# Output.net
KiCad netlist of a schematic drawn in Altium Designer
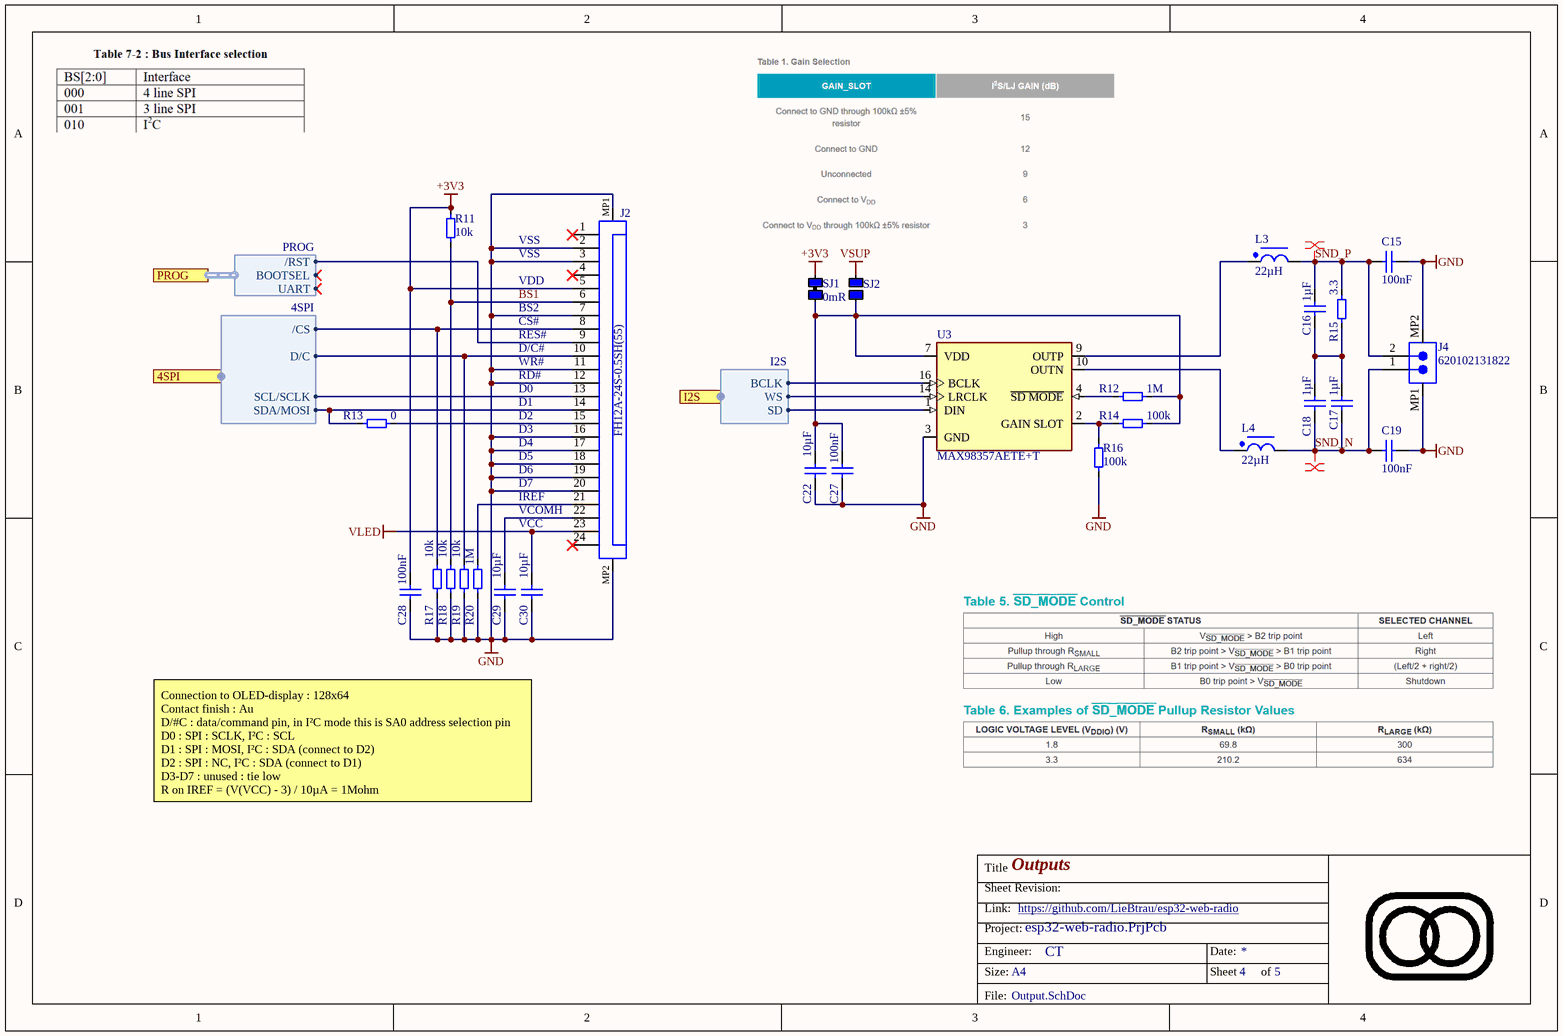
[diagram p0: Output.SchDoc]

(export (version "E")
  (design (tool "Eeschema 10.0.6"))
  (components
    (comp (ref "C15")
      (value "100nF")
      (footprint "0603-C-N")
      (description "WCAP-CSGP Multilayer Ceramic Chip Capacitor, General Purpose, size 0603, X7R, 100nF, 50VDC")
      (fields (field (name "TOLERANCE") "10%") (field (name "JLCPCB PART #") "C14663"))
      (libsource (lib "7c7 Engineering") (part "CAP-NP-2"))
    )
    (comp (ref "C16")
      (value "1µF")
      (footprint "0805-C-N")
      (description "WCAP-CSGP Multilayer Ceramic Chip Capacitor, General Purpose, size 0805, X7R, 1µF, 10VDC")
      (fields (field (name "TOLERANCE") "10%") (field (name "JLCPCB PART #") "C28323"))
      (libsource (lib "7c7 Engineering") (part "CAP-NP-2"))
    )
    (comp (ref "C17")
      (value "1µF")
      (footprint "0805-C-N")
      (description "WCAP-CSGP Multilayer Ceramic Chip Capacitor, General Purpose, size 0805, X7R, 1µF, 10VDC")
      (fields (field (name "TOLERANCE") "10%") (field (name "JLCPCB PART #") "C28323"))
      (libsource (lib "7c7 Engineering") (part "CAP-NP-2"))
    )
    (comp (ref "C18")
      (value "1µF")
      (footprint "0805-C-N")
      (description "WCAP-CSGP Multilayer Ceramic Chip Capacitor, General Purpose, size 0805, X7R, 1µF, 10VDC")
      (fields (field (name "TOLERANCE") "10%") (field (name "JLCPCB PART #") "C28323"))
      (libsource (lib "7c7 Engineering") (part "CAP-NP-2"))
    )
    (comp (ref "C19")
      (value "100nF")
      (footprint "0603-C-N")
      (description "WCAP-CSGP Multilayer Ceramic Chip Capacitor, General Purpose, size 0603, X7R, 100nF, 50VDC")
      (fields (field (name "TOLERANCE") "10%") (field (name "JLCPCB PART #") "C14663"))
      (libsource (lib "7c7 Engineering") (part "CAP-NP-2"))
    )
    (comp (ref "C22")
      (value "10µF")
      (footprint "1206-C-N")
      (description "WCAP-CSGP Multilayer Ceramic Chip Capacitor, General Purpose, size 1206, X7R, 10µF, 10VDC")
      (fields (field (name "TOLERANCE") "10%") (field (name "JLCPCB PART #") "C97953"))
      (libsource (lib "7c7 Engineering") (part "CAP-NP-2"))
    )
    (comp (ref "C27")
      (value "100nF")
      (footprint "0603-C-N")
      (description "WCAP-CSGP Multilayer Ceramic Chip Capacitor, General Purpose, size 0603, X7R, 100nF, 50VDC")
      (fields (field (name "TOLERANCE") "10%") (field (name "JLCPCB PART #") "C14663"))
      (libsource (lib "7c7 Engineering") (part "CAP-NP-2"))
    )
    (comp (ref "C28")
      (value "100nF")
      (footprint "0603-C-N")
      (description "WCAP-CSGP Multilayer Ceramic Chip Capacitor, General Purpose, size 0603, X7R, 100nF, 50VDC")
      (fields (field (name "TOLERANCE") "10%") (field (name "JLCPCB PART #") "C14663"))
      (libsource (lib "7c7 Engineering") (part "CAP-NP-2"))
    )
    (comp (ref "C29")
      (value "10µF")
      (footprint "WCAP-CSGP_1210_L3.2W2.5H2.5")
      (description "WCAP-CSGP Multilayer Ceramic Chip Capacitor, General Purpose, size 1210, X7R, 10µF, 50VDC")
      (fields (field (name "JLCPCB PART #") "C2918502") (field (name "TOLERANCE") "10%"))
      (libsource (lib "7c7 Engineering") (part "CAP-NP-2"))
    )
    (comp (ref "C30")
      (value "10µF")
      (footprint "1206-C-N")
      (description "WCAP-CSGP Multilayer Ceramic Chip Capacitor, General Purpose, size 1206, X7R, 10µF, 10VDC")
      (fields (field (name "TOLERANCE") "10%") (field (name "JLCPCB PART #") "C97953"))
      (libsource (lib "7c7 Engineering") (part "CAP-NP-2"))
    )
    (comp (ref "J2")
      (value "FH12A-24S-0.5SH(55)")
      (footprint "CF20241U0R0-NH")
      (description "Conn Ffc/fpc Connector Skt 24 Pos 0.5MM Solder Ra SMD T/r / Conn Ffc Top 24POS 0.50MM R/a")
      (fields (field (name "JLCPCB PART #") "C506794"))
      (libsource (lib "7c7 Engineering") (part "FFC_24P"))
    )
    (comp (ref "J4")
      (value "620102131822")
      (footprint "620102131822")
      (description "WR-WTB SMT Male Horizontal Shrouded Header, pitch 2mm, 2p")
      (fields (field (name "JLCPCB PART #") "C295747") (field (name "PUBLISHER") "Wurth Elektronik"))
      (libsource (lib "7c7 Engineering") (part "HDR_2P_2MP"))
    )
    (comp (ref "L3")
      (value "74404063220")
      (footprint "WE-LQS_6028")
      (description "WE-LQS SMT Power Inductor, size 6028, 22µH, 1.4A, 0.14O")
      (fields
        (field (name "INDUCTANCE") "22µH")
        (field (name "JLCPCB PART #") "C668454")
        (field (name "MANUFACTURER") "Wurth Elektronik")
      )
      (libsource (lib "7c7 Engineering") (part "IND-CORE-2"))
    )
    (comp (ref "L4")
      (value "74404063220")
      (footprint "WE-LQS_6028")
      (description "WE-LQS SMT Power Inductor, size 6028, 22µH, 1.4A, 0.14O")
      (fields
        (field (name "INDUCTANCE") "22µH")
        (field (name "JLCPCB PART #") "C668454")
        (field (name "MANUFACTURER") "Wurth Elektronik")
      )
      (libsource (lib "7c7 Engineering") (part "IND-CORE-2"))
    )
    (comp (ref "R11")
      (value "10k")
      (footprint "0603-R-N")
      (description "Chip Resistor, Thick Film, General Purpose, 0603, 100mW, 50V, 10 kOhm, +/-1%")
      (fields (field (name "JLCPCB PART #") "C25804") (field (name "TOLERANCE") "1%"))
      (libsource (lib "7c7 Engineering") (part "RES"))
    )
    (comp (ref "R12")
      (value "1M")
      (footprint "0603-R-N")
      (description "Chip Resistor, Thick Film, General Purpose, 0603, 100mW, 50V, 1 MOhm, +/-1%")
      (fields (field (name "TOLERANCE") "1%") (field (name "JLCPCB PART #") "C22935"))
      (libsource (lib "") (part "RES_1"))
    )
    (comp (ref "R13")
      (value "0")
      (footprint "0603-R-N")
      (description "Chip Jumper, Thick Film, Jumper, 0603, 100mW, 1A, 0 Ohm, <50 mOhm")
      (fields (field (name "TOLERANCE") "50 mOhm") (field (name "JLCPCB PART #") "C21189"))
      (libsource (lib "") (part "RES_1"))
    )
    (comp (ref "R14")
      (value "100k")
      (footprint "0603-R-N")
      (description "Chip Resistor, Thick Film, General Purpose, 0603, 100mW, 50V, 100 kOhm, +/-1%")
      (fields (field (name "TOLERANCE") "1%") (field (name "JLCPCB PART #") "C25803"))
      (libsource (lib "") (part "RES_2"))
    )
    (comp (ref "R15")
      (value "3.3")
      (footprint "1206-R-N")
      (description "Res Thick Film 1206 3.3 Ohm 1% 1/4W ±200ppm/°C Molded SMD SMD Paper T/R")
      (fields (field (name "JLCPCB PART #") "C17945") (field (name "TOLERANCE") "1%"))
      (libsource (lib "7c7 Engineering") (part "RES"))
    )
    (comp (ref "R16")
      (value "100k")
      (footprint "0603-R-N")
      (description "Chip Resistor, Thick Film, General Purpose, 0603, 100mW, 50V, 100 kOhm, +/-1%")
      (fields (field (name "TOLERANCE") "1%") (field (name "JLCPCB PART #") "C25803"))
      (libsource (lib "7c7 Engineering") (part "RES"))
    )
    (comp (ref "R17")
      (value "10k")
      (footprint "0603-R-N")
      (description "Chip Resistor, Thick Film, General Purpose, 0603, 100mW, 50V, 10 kOhm, +/-1%")
      (fields (field (name "JLCPCB PART #") "C25804") (field (name "TOLERANCE") "1%"))
      (libsource (lib "7c7 Engineering") (part "RES"))
    )
    (comp (ref "R18")
      (value "10k")
      (footprint "0603-R-N")
      (description "Chip Resistor, Thick Film, General Purpose, 0603, 100mW, 50V, 10 kOhm, +/-1%")
      (fields (field (name "JLCPCB PART #") "C25804") (field (name "TOLERANCE") "1%"))
      (libsource (lib "7c7 Engineering") (part "RES"))
    )
    (comp (ref "R19")
      (value "10k")
      (footprint "0603-R-N")
      (description "Chip Resistor, Thick Film, General Purpose, 0603, 100mW, 50V, 10 kOhm, +/-1%")
      (fields (field (name "JLCPCB PART #") "C25804") (field (name "TOLERANCE") "1%"))
      (libsource (lib "7c7 Engineering") (part "RES"))
    )
    (comp (ref "R20")
      (value "1M")
      (footprint "0603-R-N")
      (description "Chip Resistor, Thick Film, General Purpose, 0603, 100mW, 50V, 1 MOhm, +/-1%")
      (fields (field (name "TOLERANCE") "1%") (field (name "JLCPCB PART #") "C22935"))
      (libsource (lib "7c7 Engineering") (part "RES"))
    )
    (comp (ref "SJ1")
      (value "0mR")
      (footprint "SJ_0603_1A")
      (description "Solder jumper 0603 1A")
      (fields (field (name "JLCPCB PART #") "C876125") (field (name "TOLERANCE") "1%"))
      (libsource (lib "7c7 Engineering") (part "SJ-C"))
    )
    (comp (ref "SJ2")
      (value "Solder jumper open 1A")
      (footprint "Solder jumper open 1A-Footprint-1")
      (libsource (lib "7c7 Engineering") (part "SJ-O"))
    )
    (comp (ref "U3")
      (value "MAX98357AETE+T")
      (footprint "TQFN16-MFG")
      (description "IC AUDIO AMP CLASS D 16-TQFN")
      (fields (field (name "JLCPCB PART #") "C910544"))
      (libsource (lib "7c7 Engineering") (part "MAX98357A"))
    )
  )
  (nets
    (net (code "4") (name "+3V3") (class "Default")
      (node (ref "C28") (pin "1") (pinfunction "1_1") (pintype "passive"))
      (node (ref "J2") (pin "5") (pinfunction "5_5") (pintype "passive"))
      (node (ref "R11") (pin "2") (pinfunction "2_2") (pintype "passive"))
      (node (ref "SJ1") (pin "2") (pinfunction "R_2") (pintype "passive"))
    )
    (net (code "5") (name "/BS1") (class "Default")
      (node (ref "J2") (pin "6") (pinfunction "6_6") (pintype "passive"))
      (node (ref "R11") (pin "1") (pinfunction "1_1") (pintype "passive"))
      (node (ref "R18") (pin "2") (pinfunction "2_2") (pintype "passive"))
    )
    (net (code "6") (name "/SND_N") (class "Default")
      (node (ref "C17") (pin "1") (pinfunction "1_1") (pintype "passive"))
      (node (ref "C18") (pin "1") (pinfunction "1_1") (pintype "passive"))
      (node (ref "C19") (pin "1") (pinfunction "1_1") (pintype "passive"))
      (node (ref "J4") (pin "1") (pinfunction "1_1") (pintype "passive"))
      (node (ref "L4") (pin "2") (pinfunction "2_2") (pintype "passive"))
    )
    (net (code "7") (name "/SND_P") (class "Default")
      (node (ref "C15") (pin "1") (pinfunction "1_1") (pintype "passive"))
      (node (ref "C16") (pin "2") (pinfunction "2_2") (pintype "passive"))
      (node (ref "J4") (pin "2") (pinfunction "2_2") (pintype "passive"))
      (node (ref "L3") (pin "2") (pinfunction "2_2") (pintype "passive"))
      (node (ref "R15") (pin "2") (pinfunction "2_2") (pintype "passive"))
    )
    (net (code "11") (name "GND") (class "Default")
      (node (ref "C15") (pin "2") (pinfunction "2_2") (pintype "passive"))
      (node (ref "C19") (pin "2") (pinfunction "2_2") (pintype "passive"))
      (node (ref "C22") (pin "1") (pinfunction "1_1") (pintype "passive"))
      (node (ref "C27") (pin "1") (pinfunction "1_1") (pintype "passive"))
      (node (ref "C28") (pin "2") (pinfunction "2_2") (pintype "passive"))
      (node (ref "C29") (pin "1") (pinfunction "1_1") (pintype "passive"))
      (node (ref "C30") (pin "1") (pinfunction "1_1") (pintype "passive"))
      (node (ref "J2") (pin "11") (pinfunction "11_11") (pintype "passive"))
      (node (ref "J2") (pin "12") (pinfunction "12_12") (pintype "passive"))
      (node (ref "J2") (pin "16") (pinfunction "16_16") (pintype "passive"))
      (node (ref "J2") (pin "17") (pinfunction "17_17") (pintype "passive"))
      (node (ref "J2") (pin "18") (pinfunction "18_18") (pintype "passive"))
      (node (ref "J2") (pin "19") (pinfunction "19_19") (pintype "passive"))
      (node (ref "J2") (pin "2") (pinfunction "2_2") (pintype "passive"))
      (node (ref "J2") (pin "20") (pinfunction "20_20") (pintype "passive"))
      (node (ref "J2") (pin "3") (pinfunction "3_3") (pintype "passive"))
      (node (ref "J2") (pin "7") (pinfunction "7_7") (pintype "passive"))
      (node (ref "J2") (pin "MP1") (pinfunction "MP1_MP1") (pintype "passive"))
      (node (ref "J2") (pin "MP2") (pinfunction "MP2_MP2") (pintype "passive"))
      (node (ref "J4") (pin "MP1") (pinfunction "MP1_MP1") (pintype "passive"))
      (node (ref "J4") (pin "MP2") (pinfunction "MP2_MP2") (pintype "passive"))
      (node (ref "R16") (pin "1") (pinfunction "1_1") (pintype "passive"))
      (node (ref "R17") (pin "1") (pinfunction "1_1") (pintype "passive"))
      (node (ref "R18") (pin "1") (pinfunction "1_1") (pintype "passive"))
      (node (ref "R19") (pin "1") (pinfunction "1_1") (pintype "passive"))
      (node (ref "R20") (pin "1") (pinfunction "1_1") (pintype "passive"))
      (node (ref "U3") (pin "3") (pinfunction "GND_3") (pintype "power_in"))
    )
    (net (code "12") (name "Net-(C16-Pad1)") (class "Default")
      (node (ref "C16") (pin "1") (pinfunction "1_1") (pintype "passive"))
      (node (ref "C17") (pin "2") (pinfunction "2_2") (pintype "passive"))
      (node (ref "C18") (pin "2") (pinfunction "2_2") (pintype "passive"))
      (node (ref "R15") (pin "1") (pinfunction "1_1") (pintype "passive"))
    )
    (net (code "13") (name "Net-(C29-Pad2)") (class "Default")
      (node (ref "C29") (pin "2") (pinfunction "2_2") (pintype "passive"))
      (node (ref "J2") (pin "22") (pinfunction "22_22") (pintype "passive"))
    )
    (net (code "14") (name "Net-(J2-Pad8)") (class "Default")
      (node (ref "J2") (pin "8") (pinfunction "8_8") (pintype "passive"))
      (node (ref "R17") (pin "2") (pinfunction "2_2") (pintype "passive"))
    )
    (net (code "15") (name "Net-(J2-Pad10)") (class "Default")
      (node (ref "J2") (pin "10") (pinfunction "10_10") (pintype "passive"))
      (node (ref "R19") (pin "2") (pinfunction "2_2") (pintype "passive"))
    )
    (net (code "16") (name "Net-(J2-Pad14)") (class "Default")
      (node (ref "J2") (pin "14") (pinfunction "14_14") (pintype "passive"))
      (node (ref "R13") (pin "2") (pinfunction "2_2") (pintype "passive"))
    )
    (net (code "17") (name "Net-(J2-Pad15)") (class "Default")
      (node (ref "J2") (pin "15") (pinfunction "15_15") (pintype "passive"))
      (node (ref "R13") (pin "1") (pinfunction "1_1") (pintype "passive"))
    )
    (net (code "18") (name "Net-(J2-Pad21)") (class "Default")
      (node (ref "J2") (pin "21") (pinfunction "21_21") (pintype "passive"))
      (node (ref "R20") (pin "2") (pinfunction "2_2") (pintype "passive"))
    )
    (net (code "19") (name "Net-(SJ1-L)") (class "Default")
      (node (ref "C22") (pin "2") (pinfunction "2_2") (pintype "passive"))
      (node (ref "C27") (pin "2") (pinfunction "2_2") (pintype "passive"))
      (node (ref "R12") (pin "1") (pinfunction "1_1") (pintype "passive"))
      (node (ref "R14") (pin "2") (pinfunction "2_2") (pintype "passive"))
      (node (ref "SJ1") (pin "1") (pinfunction "L_1") (pintype "passive"))
      (node (ref "SJ2") (pin "1") (pinfunction "L_1") (pintype "passive"))
      (node (ref "U3") (pin "7") (pinfunction "VDD_7") (pintype "power_in"))
    )
    (net (code "20") (name "Net-(U3-GAIN_SLOT)") (class "Default")
      (node (ref "R14") (pin "1") (pinfunction "1_1") (pintype "passive"))
      (node (ref "R16") (pin "2") (pinfunction "2_2") (pintype "passive"))
      (node (ref "U3") (pin "2") (pinfunction "GAIN_SLOT_2") (pintype "passive"))
    )
    (net (code "21") (name "Net-(U3-OUTN)") (class "Default")
      (node (ref "L4") (pin "1") (pinfunction "1_1") (pintype "passive"))
      (node (ref "U3") (pin "10") (pinfunction "OUTN_10") (pintype "passive"))
    )
    (net (code "22") (name "Net-(U3-OUTP)") (class "Default")
      (node (ref "L3") (pin "1") (pinfunction "1_1") (pintype "passive"))
      (node (ref "U3") (pin "9") (pinfunction "OUTP_9") (pintype "passive"))
    )
    (net (code "23") (name "Net-(U3-~{SD_MODE})") (class "Default")
      (node (ref "R12") (pin "2") (pinfunction "2_2") (pintype "passive"))
      (node (ref "U3") (pin "4") (pinfunction "~{SD_MODE}_4") (pintype "input"))
    )
    (net (code "24") (name "VLED") (class "Default")
      (node (ref "C30") (pin "2") (pinfunction "2_2") (pintype "passive"))
      (node (ref "J2") (pin "23") (pinfunction "23_23") (pintype "passive"))
    )
    (net (code "25") (name "VSUP") (class "Default")
      (node (ref "SJ2") (pin "2") (pinfunction "R_2") (pintype "passive"))
    )
    (net (code "26") (name "unconnected-(J2-Pad1)") (class "Default")
      (node (ref "J2") (pin "1") (pinfunction "1_1") (pintype "passive+no_connect"))
    )
    (net (code "27") (name "unconnected-(J2-Pad4)") (class "Default")
      (node (ref "J2") (pin "4") (pinfunction "4_4") (pintype "passive+no_connect"))
    )
    (net (code "28") (name "unconnected-(J2-Pad9)") (class "Default")
      (node (ref "J2") (pin "9") (pinfunction "9_9") (pintype "passive"))
    )
    (net (code "29") (name "unconnected-(J2-Pad13)") (class "Default")
      (node (ref "J2") (pin "13") (pinfunction "13_13") (pintype "passive"))
    )
    (net (code "30") (name "unconnected-(J2-Pad24)") (class "Default")
      (node (ref "J2") (pin "24") (pinfunction "24_24") (pintype "passive+no_connect"))
    )
    (net (code "31") (name "unconnected-(U3-BCLK-Pad16)") (class "Default")
      (node (ref "U3") (pin "16") (pinfunction "BCLK_16") (pintype "input"))
    )
    (net (code "32") (name "unconnected-(U3-DIN-Pad1)") (class "Default")
      (node (ref "U3") (pin "1") (pinfunction "DIN_1") (pintype "input"))
    )
    (net (code "33") (name "unconnected-(U3-LRCLK-Pad14)") (class "Default")
      (node (ref "U3") (pin "14") (pinfunction "LRCLK_14") (pintype "input"))
    )
  )
)
